# pulse_generator.net
KiCad netlist of a schematic drawn in Altium Designer
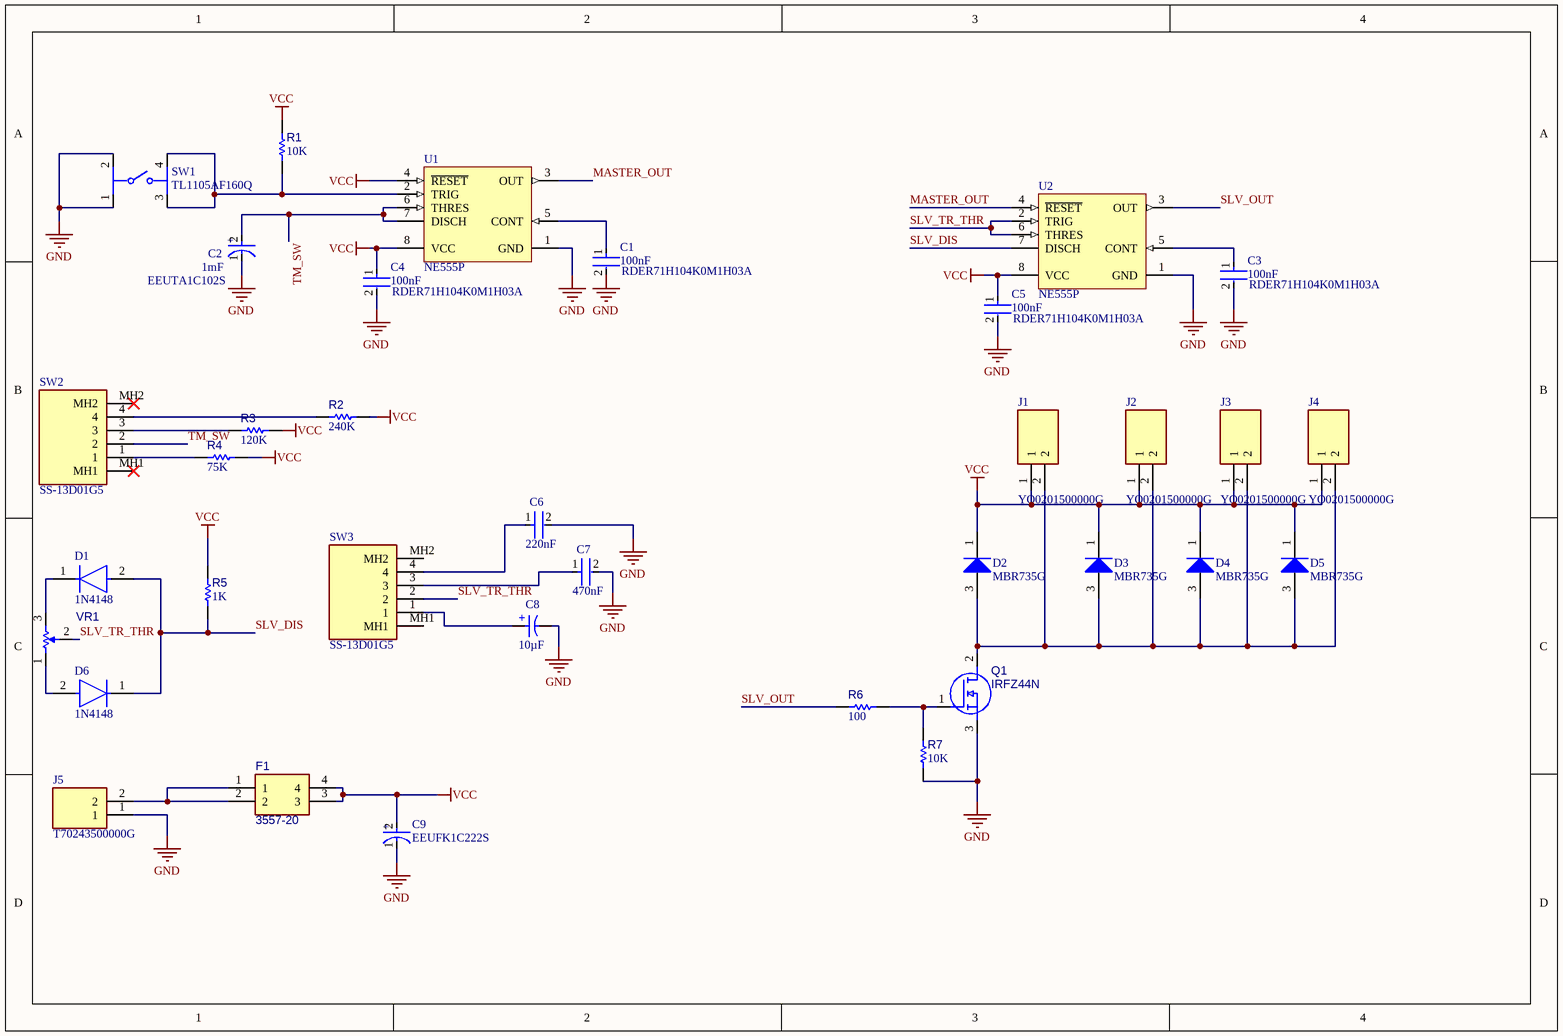
[diagram p0: pulse_generator.SchDoc]

(export (version "E")
  (design (tool "Eeschema 10.0.6"))
  (components
    (comp (ref "C1")
      (value "RDER71H104K0M1H03A")
      (footprint "FP-RDE0M1-MFG")
      (description "Ceramic Capacitor 100nF ±10% 50V X7R Radial")
      (fields (field (name "CAPACITANCE") "100nF") (field (name "TOLERANCE") "10%"))
      (libsource (lib "Altium Content Vault") (part "b4654b650e69147ec39a6b967a45e02"))
    )
    (comp (ref "C2")
      (value "EEUTA1C102S")
      (footprint "FP-RAD-TH-D_16_0_5-L_15_1-MFG")
      (description "Aluminum Electrolytic Capacitors (Radial Lead Type) AEC-Q200 Qualified 1000uF ±20% 16V")
      (fields (field (name "TOLERANCE") "20%") (field (name "CAPACITANCE") "1mF"))
      (libsource (lib "Altium Content Vault") (part "a00bbbee19879c290e62620ae7e47b1"))
    )
    (comp (ref "C3")
      (value "RDER71H104K0M1H03A")
      (footprint "FP-RDE0M1-MFG")
      (description "Ceramic Capacitor 100nF ±10% 50V X7R Radial")
      (fields (field (name "CAPACITANCE") "100nF") (field (name "TOLERANCE") "10%"))
      (libsource (lib "Altium Content Vault") (part "b4654b650e69147ec39a6b967a45e02"))
    )
    (comp (ref "C4")
      (value "RDER71H104K0M1H03A")
      (footprint "FP-RDE0M1-MFG")
      (description "Ceramic Capacitor 100nF ±10% 50V X7R Radial")
      (fields (field (name "CAPACITANCE") "100nF") (field (name "TOLERANCE") "10%"))
      (libsource (lib "Altium Content Vault") (part "b4654b650e69147ec39a6b967a45e02"))
    )
    (comp (ref "C5")
      (value "RDER71H104K0M1H03A")
      (footprint "FP-RDE0M1-MFG")
      (description "Ceramic Capacitor 100nF ±10% 50V X7R Radial")
      (fields (field (name "CAPACITANCE") "100nF") (field (name "TOLERANCE") "10%"))
      (libsource (lib "Altium Content Vault") (part "b4654b650e69147ec39a6b967a45e02"))
    )
    (comp (ref "C6")
      (value "RCER71H224K1DBH03A")
      (footprint "FP-RCE1A2-MFG")
      (description "Cap Ceramic 220nF 50V X7R ±10% Radial 2.5mm +125°C Automotive Ammo Pack")
      (fields (field (name "CAPACITANCE") "220nF") (field (name "TOLERANCE") "10%"))
      (libsource (lib "Altium Content Vault") (part "02cd4be3c70576c341d710602a673aa"))
    )
    (comp (ref "C7")
      (value "RCER71H474K1A2H03B")
      (footprint "FP-RCE1A2-MFG")
      (description "Cap Ceramic 470nF 50V X7R ±10% Radial 2.5mm +125°C Automotive Bulk")
      (fields (field (name "TOLERANCE") "10%") (field (name "CAPACITANCE") "470nF"))
      (libsource (lib "Altium Content Vault") (part "02cd4be3c70576c341d710602a673aa"))
    )
    (comp (ref "C8")
      (value "860020372001")
      (footprint "WCAP-ATG5_D5H11")
      (description "WCAP-ATG5 Aluminum Electrolytic Capacitors")
      (fields (field (name "TOLERANCE") "20%") (field (name "CAPACITANCE") "10µF"))
      (libsource (lib "Altium Content Vault") (part "Capacitor_Polarized"))
    )
    (comp (ref "C9")
      (value "EEUFK1C222S")
      (footprint "FP-RAD-TH-D_16_0_5-L_15_1-MFG")
      (description "Aluminum Electrolytic Capacitors (Radial Lead Type) AEC-Q200 Qualified 2200uF ±20% 16V")
      (fields (field (name "VOLTAGE") "16V") (field (name "TOLERANCE") "20%"))
      (libsource (lib "Altium Content Vault") (part "a00bbbee19879c290e62620ae7e47b1"))
    )
    (comp (ref "D1")
      (value "1N4148")
      (footprint "FP-017AG-MFG")
      (description "DIODE GEN PURP 100V 200MA DO35")
      (fields (field (name "VOLTAGE") "100V"))
      (libsource (lib "Altium Content Vault") (part "d7152d700b627762746794eb795d46e"))
    )
    (comp (ref "D2")
      (value "MBR735G")
      (footprint "ONSC-TO-220-2-221B-04_E")
      (description "SWITCHMODE(TM) Power Rectifier, 2-Pin TO-220, Pb-Free, Tube")
      (fields (field (name "MANUFACTURER") "On Semiconductor"))
      (libsource (lib "Altium Content Vault") (part "ONSC-D-K1A3-2_A"))
    )
    (comp (ref "D3")
      (value "MBR735G")
      (footprint "ONSC-TO-220-2-221B-04_E")
      (description "SWITCHMODE(TM) Power Rectifier, 2-Pin TO-220, Pb-Free, Tube")
      (fields (field (name "MANUFACTURER") "On Semiconductor"))
      (libsource (lib "Altium Content Vault") (part "ONSC-D-K1A3-2_A"))
    )
    (comp (ref "D4")
      (value "MBR735G")
      (footprint "ONSC-TO-220-2-221B-04_E")
      (description "SWITCHMODE(TM) Power Rectifier, 2-Pin TO-220, Pb-Free, Tube")
      (fields (field (name "MANUFACTURER") "On Semiconductor"))
      (libsource (lib "Altium Content Vault") (part "ONSC-D-K1A3-2_A"))
    )
    (comp (ref "D5")
      (value "MBR735G")
      (footprint "ONSC-TO-220-2-221B-04_E")
      (description "SWITCHMODE(TM) Power Rectifier, 2-Pin TO-220, Pb-Free, Tube")
      (fields (field (name "MANUFACTURER") "On Semiconductor"))
      (libsource (lib "Altium Content Vault") (part "ONSC-D-K1A3-2_A"))
    )
    (comp (ref "D6")
      (value "1N4148")
      (footprint "FP-017AG-MFG")
      (description "DIODE GEN PURP 100V 200MA DO35")
      (fields (field (name "VOLTAGE") "100V"))
      (libsource (lib "Altium Content Vault") (part "d7152d700b627762746794eb795d46e"))
    )
    (comp (ref "F1")
      (value "3557-20")
      (footprint "3557-20-Footprint-1")
      (description "Fuse Holder T/H 2 IN 1 AUTO BLDE HOLDER, YELLOW 20A")
      (libsource (lib "Szymon Dobrowolski") (part "FUSE"))
    )
    (comp (ref "J1")
      (value "YO0201500000G")
      (footprint "YO0201500000G-Footprint-1")
      (description "Conn Terminal Block 2 POS 3.5mm Solder ST Thru-Hole 10A/Contact Box")
      (libsource (lib "Szymon Dobrowolski") (part "YO0201500000G"))
    )
    (comp (ref "J2")
      (value "YO0201500000G")
      (footprint "YO0201500000G-Footprint-1")
      (description "Conn Terminal Block 2 POS 3.5mm Solder ST Thru-Hole 10A/Contact Box")
      (libsource (lib "Szymon Dobrowolski") (part "YO0201500000G"))
    )
    (comp (ref "J3")
      (value "YO0201500000G")
      (footprint "YO0201500000G-Footprint-1")
      (description "Conn Terminal Block 2 POS 3.5mm Solder ST Thru-Hole 10A/Contact Box")
      (libsource (lib "Szymon Dobrowolski") (part "YO0201500000G"))
    )
    (comp (ref "J4")
      (value "YO0201500000G")
      (footprint "YO0201500000G-Footprint-1")
      (description "Conn Terminal Block 2 POS 3.5mm Solder ST Thru-Hole 10A/Contact Box")
      (libsource (lib "Szymon Dobrowolski") (part "YO0201500000G"))
    )
    (comp (ref "J5")
      (value "T70243500000G")
      (footprint "T70243500000G-Footprint-1")
      (description "Terminal Block 2P")
      (libsource (lib "Szymon Dobrowolski") (part "T70243500000G"))
    )
    (comp (ref "Q1")
      (value "IRFZ44N")
      (footprint "IRFZ44N-Footprint-1")
      (description "N-Channel MOSFET Transistor")
      (libsource (lib "Szymon Dobrowolski") (part "IRFZ44N"))
    )
    (comp (ref "R1")
      (value "10K")
      (footprint "Resistor THT 0.4-Footprint-1")
      (description "Resistor THT axial 0.4")
      (fields (field (name "Comment") "Resistor THT 0.4"))
      (libsource (lib "Szymon Dobrowolski") (part "RES"))
    )
    (comp (ref "R2")
      (value "240K")
      (footprint "Resistor THT 0.4-Footprint-1")
      (description "Resistor THT axial 0.4")
      (fields (field (name "Comment") "Resistor THT 0.4"))
      (libsource (lib "Szymon Dobrowolski") (part "RES"))
    )
    (comp (ref "R3")
      (value "120K")
      (footprint "Resistor THT 0.4-Footprint-1")
      (description "Resistor THT axial 0.4")
      (fields (field (name "Comment") "Resistor THT 0.4"))
      (libsource (lib "Szymon Dobrowolski") (part "RES"))
    )
    (comp (ref "R4")
      (value "75K")
      (footprint "Resistor THT 0.4-Footprint-1")
      (description "Resistor THT axial 0.4")
      (fields (field (name "Comment") "Resistor THT 0.4"))
      (libsource (lib "Szymon Dobrowolski") (part "RES"))
    )
    (comp (ref "R5")
      (value "1K")
      (footprint "Resistor THT 0.4-Footprint-1")
      (description "Resistor THT axial 0.4")
      (fields (field (name "Comment") "Resistor THT 0.4"))
      (libsource (lib "Szymon Dobrowolski") (part "RES"))
    )
    (comp (ref "R6")
      (value "100")
      (footprint "Resistor THT 0.4-Footprint-1")
      (description "Resistor THT axial 0.4")
      (fields (field (name "Comment") "Resistor THT 0.4"))
      (libsource (lib "Szymon Dobrowolski") (part "RES"))
    )
    (comp (ref "R7")
      (value "10K")
      (footprint "Resistor THT 0.4-Footprint-1")
      (description "Resistor THT axial 0.4")
      (fields (field (name "Comment") "Resistor THT 0.4"))
      (libsource (lib "Szymon Dobrowolski") (part "RES"))
    )
    (comp (ref "SW1")
      (value "TL1105AF160Q")
      (footprint "FP-TL1105AF160Q-MFG")
      (description "SWITCH TACTILE SPST-NO 0.05A 12V")
      (libsource (lib "Altium Content Vault") (part "82b636f13fd696edb7519609c0a8a76"))
    )
    (comp (ref "SW2")
      (value "SS-13D01G5")
      (footprint "SS-13D01G5-Footprint-1")
      (description "Switch Slide 3 Position SP3T")
      (libsource (lib "Szymon Dobrowolski") (part "SS-13D01G5"))
    )
    (comp (ref "SW3")
      (value "SS-13D01G5")
      (footprint "SS-13D01G5-Footprint-1")
      (description "Switch Slide 3 Position SP3T")
      (libsource (lib "Szymon Dobrowolski") (part "SS-13D01G5"))
    )
    (comp (ref "U1")
      (value "NE555P")
      (footprint "P0008A")
      (description "Precision Timer, 4.5 to 16 V, 0 to 70 degC, 8-Pin DIP, Pb-Free, Tube")
      (fields (field (name "MANUFACTURER") "TexasInstruments"))
      (libsource (lib "Altium Content Vault") (part "TI-NE555-P8"))
    )
    (comp (ref "U2")
      (value "NE555P")
      (footprint "P0008A")
      (description "Precision Timer, 4.5 to 16 V, 0 to 70 degC, 8-Pin DIP, Pb-Free, Tube")
      (fields (field (name "MANUFACTURER") "TexasInstruments"))
      (libsource (lib "Altium Content Vault") (part "TI-NE555-P8"))
    )
    (comp (ref "VR1")
      (value "Potentiometer_100k")
      (footprint "New footprint 1")
      (description "Potencjometr osiowy 100k liniowy PCB")
      (libsource (lib "Szymon Dobrowolski") (part "POTENTIOMETER"))
    )
  )
  (nets
    (net (code "1") (name "/MASTER_OUT") (class "Default")
      (node (ref "U1") (pin "3") (pinfunction "OUT_3") (pintype "output"))
      (node (ref "U2") (pin "4") (pinfunction "~{RESET}_4") (pintype "input"))
    )
    (net (code "2") (name "/SLV_DIS") (class "Default")
      (node (ref "D1") (pin "2") (pinfunction "A_2") (pintype "passive"))
      (node (ref "D6") (pin "1") (pinfunction "C_1") (pintype "passive"))
      (node (ref "R5") (pin "1") (pinfunction "A_1") (pintype "passive"))
      (node (ref "U2") (pin "7") (pinfunction "DISCH_7") (pintype "open_collector"))
    )
    (net (code "3") (name "/SLV_OUT") (class "Default")
      (node (ref "R6") (pin "2") (pinfunction "B_2") (pintype "passive"))
      (node (ref "U2") (pin "3") (pinfunction "OUT_3") (pintype "output"))
    )
    (net (code "4") (name "/SLV_TR_THR") (class "Default")
      (node (ref "SW3") (pin "2") (pinfunction "2_2") (pintype "passive"))
      (node (ref "U2") (pin "2") (pinfunction "TRIG_2") (pintype "input"))
      (node (ref "U2") (pin "6") (pinfunction "THRES_6") (pintype "input"))
      (node (ref "VR1") (pin "2") (pinfunction "TAP_2") (pintype "passive"))
    )
    (net (code "5") (name "/TM_SW") (class "Default")
      (node (ref "C2") (pin "2") (pinfunction "A_2") (pintype "passive"))
      (node (ref "SW2") (pin "2") (pinfunction "2_2") (pintype "passive"))
      (node (ref "U1") (pin "6") (pinfunction "THRES_6") (pintype "input"))
      (node (ref "U1") (pin "7") (pinfunction "DISCH_7") (pintype "open_collector"))
    )
    (net (code "6") (name "GND") (class "Default")
      (node (ref "C1") (pin "2") (pinfunction "2_2") (pintype "passive"))
      (node (ref "C2") (pin "1") (pinfunction "C_1") (pintype "passive"))
      (node (ref "C3") (pin "2") (pinfunction "2_2") (pintype "passive"))
      (node (ref "C4") (pin "2") (pinfunction "2_2") (pintype "passive"))
      (node (ref "C5") (pin "2") (pinfunction "2_2") (pintype "passive"))
      (node (ref "C6") (pin "2") (pinfunction "2_2") (pintype "passive"))
      (node (ref "C7") (pin "2") (pinfunction "2_2") (pintype "passive"))
      (node (ref "C8") (pin "2") (pinfunction "N_2") (pintype "passive"))
      (node (ref "C9") (pin "1") (pinfunction "C_1") (pintype "passive"))
      (node (ref "J5") (pin "1") (pinfunction "1_1") (pintype "passive"))
      (node (ref "Q1") (pin "3") (pinfunction "S_3") (pintype "passive"))
      (node (ref "R7") (pin "1") (pinfunction "A_1") (pintype "passive"))
      (node (ref "SW1") (pin "1") (pinfunction "1_1") (pintype "passive"))
      (node (ref "SW1") (pin "2") (pinfunction "2_2") (pintype "passive"))
      (node (ref "U1") (pin "1") (pinfunction "GND_1") (pintype "power_in"))
      (node (ref "U2") (pin "1") (pinfunction "GND_1") (pintype "power_in"))
    )
    (net (code "7") (name "Net-(C6-Pad1)") (class "Default")
      (node (ref "C6") (pin "1") (pinfunction "1_1") (pintype "passive"))
      (node (ref "SW3") (pin "4") (pinfunction "4_4") (pintype "passive"))
    )
    (net (code "8") (name "Net-(C7-Pad1)") (class "Default")
      (node (ref "C7") (pin "1") (pinfunction "1_1") (pintype "passive"))
      (node (ref "SW3") (pin "3") (pinfunction "3_3") (pintype "passive"))
    )
    (net (code "9") (name "Net-(C8-P)") (class "Default")
      (node (ref "C8") (pin "1") (pinfunction "P_1") (pintype "passive"))
      (node (ref "SW3") (pin "1") (pinfunction "1_1") (pintype "passive"))
    )
    (net (code "10") (name "Net-(D1-C)") (class "Default")
      (node (ref "D1") (pin "1") (pinfunction "C_1") (pintype "passive"))
      (node (ref "VR1") (pin "3") (pinfunction "B_3") (pintype "passive"))
    )
    (net (code "11") (name "Net-(D2-A)") (class "Default")
      (node (ref "D2") (pin "3") (pinfunction "A_3") (pintype "passive"))
      (node (ref "D3") (pin "3") (pinfunction "A_3") (pintype "passive"))
      (node (ref "D4") (pin "3") (pinfunction "A_3") (pintype "passive"))
      (node (ref "D5") (pin "3") (pinfunction "A_3") (pintype "passive"))
      (node (ref "J1") (pin "2") (pinfunction "2_2") (pintype "passive"))
      (node (ref "J2") (pin "2") (pinfunction "2_2") (pintype "passive"))
      (node (ref "J3") (pin "2") (pinfunction "2_2") (pintype "passive"))
      (node (ref "J4") (pin "2") (pinfunction "2_2") (pintype "passive"))
      (node (ref "Q1") (pin "2") (pinfunction "D_2") (pintype "passive"))
    )
    (net (code "12") (name "Net-(D6-A)") (class "Default")
      (node (ref "D6") (pin "2") (pinfunction "A_2") (pintype "passive"))
      (node (ref "VR1") (pin "1") (pinfunction "A_1") (pintype "passive"))
    )
    (net (code "13") (name "Net-(F1-Pad1)") (class "Default")
      (node (ref "F1") (pin "1") (pinfunction "1_1") (pintype "passive"))
      (node (ref "F1") (pin "2") (pinfunction "2_2") (pintype "passive"))
      (node (ref "J5") (pin "2") (pinfunction "2_2") (pintype "passive"))
    )
    (net (code "14") (name "Net-(Q1-G)") (class "Default")
      (node (ref "Q1") (pin "1") (pinfunction "G_1") (pintype "passive"))
      (node (ref "R6") (pin "1") (pinfunction "A_1") (pintype "passive"))
      (node (ref "R7") (pin "2") (pinfunction "B_2") (pintype "passive"))
    )
    (net (code "15") (name "Net-(R1-A)") (class "Default")
      (node (ref "R1") (pin "1") (pinfunction "A_1") (pintype "passive"))
      (node (ref "SW1") (pin "3") (pinfunction "3_3") (pintype "passive"))
      (node (ref "SW1") (pin "4") (pinfunction "4_4") (pintype "passive"))
      (node (ref "U1") (pin "2") (pinfunction "TRIG_2") (pintype "input"))
    )
    (net (code "16") (name "Net-(R2-B)") (class "Default")
      (node (ref "R2") (pin "2") (pinfunction "B_2") (pintype "passive"))
      (node (ref "SW2") (pin "4") (pinfunction "4_4") (pintype "passive"))
    )
    (net (code "17") (name "Net-(R3-B)") (class "Default")
      (node (ref "R3") (pin "2") (pinfunction "B_2") (pintype "passive"))
      (node (ref "SW2") (pin "3") (pinfunction "3_3") (pintype "passive"))
    )
    (net (code "18") (name "Net-(R4-B)") (class "Default")
      (node (ref "R4") (pin "2") (pinfunction "B_2") (pintype "passive"))
      (node (ref "SW2") (pin "1") (pinfunction "1_1") (pintype "passive"))
    )
    (net (code "19") (name "Net-(U1-CONT)") (class "Default")
      (node (ref "C1") (pin "1") (pinfunction "1_1") (pintype "passive"))
      (node (ref "U1") (pin "5") (pinfunction "CONT_5") (pintype "input"))
    )
    (net (code "20") (name "Net-(U2-CONT)") (class "Default")
      (node (ref "C3") (pin "1") (pinfunction "1_1") (pintype "passive"))
      (node (ref "U2") (pin "5") (pinfunction "CONT_5") (pintype "input"))
    )
    (net (code "21") (name "VCC") (class "Default")
      (node (ref "C4") (pin "1") (pinfunction "1_1") (pintype "passive"))
      (node (ref "C5") (pin "1") (pinfunction "1_1") (pintype "passive"))
      (node (ref "C9") (pin "2") (pinfunction "A_2") (pintype "passive"))
      (node (ref "D2") (pin "1") (pinfunction "K_1") (pintype "passive"))
      (node (ref "D3") (pin "1") (pinfunction "K_1") (pintype "passive"))
      (node (ref "D4") (pin "1") (pinfunction "K_1") (pintype "passive"))
      (node (ref "D5") (pin "1") (pinfunction "K_1") (pintype "passive"))
      (node (ref "F1") (pin "3") (pinfunction "3_3") (pintype "passive"))
      (node (ref "F1") (pin "4") (pinfunction "4_4") (pintype "passive"))
      (node (ref "J1") (pin "1") (pinfunction "1_1") (pintype "passive"))
      (node (ref "J2") (pin "1") (pinfunction "1_1") (pintype "passive"))
      (node (ref "J3") (pin "1") (pinfunction "1_1") (pintype "passive"))
      (node (ref "J4") (pin "1") (pinfunction "1_1") (pintype "passive"))
      (node (ref "R1") (pin "2") (pinfunction "B_2") (pintype "passive"))
      (node (ref "R2") (pin "1") (pinfunction "A_1") (pintype "passive"))
      (node (ref "R3") (pin "1") (pinfunction "A_1") (pintype "passive"))
      (node (ref "R4") (pin "1") (pinfunction "A_1") (pintype "passive"))
      (node (ref "R5") (pin "2") (pinfunction "B_2") (pintype "passive"))
      (node (ref "U1") (pin "4") (pinfunction "~{RESET}_4") (pintype "input"))
      (node (ref "U1") (pin "8") (pinfunction "VCC_8") (pintype "power_in"))
      (node (ref "U2") (pin "8") (pinfunction "VCC_8") (pintype "power_in"))
    )
    (net (code "22") (name "unconnected-(SW2-PadMH1)") (class "Default")
      (node (ref "SW2") (pin "MH1") (pinfunction "MH1_MH1") (pintype "passive+no_connect"))
    )
    (net (code "23") (name "unconnected-(SW2-PadMH2)") (class "Default")
      (node (ref "SW2") (pin "MH2") (pinfunction "MH2_MH2") (pintype "passive+no_connect"))
    )
    (net (code "24") (name "unconnected-(SW3-PadMH1)") (class "Default")
      (node (ref "SW3") (pin "MH1") (pinfunction "MH1_MH1") (pintype "passive"))
    )
    (net (code "25") (name "unconnected-(SW3-PadMH2)") (class "Default")
      (node (ref "SW3") (pin "MH2") (pinfunction "MH2_MH2") (pintype "passive"))
    )
  )
)
